# iF11M.net
KiCad netlist of a schematic drawn in Altium Designer
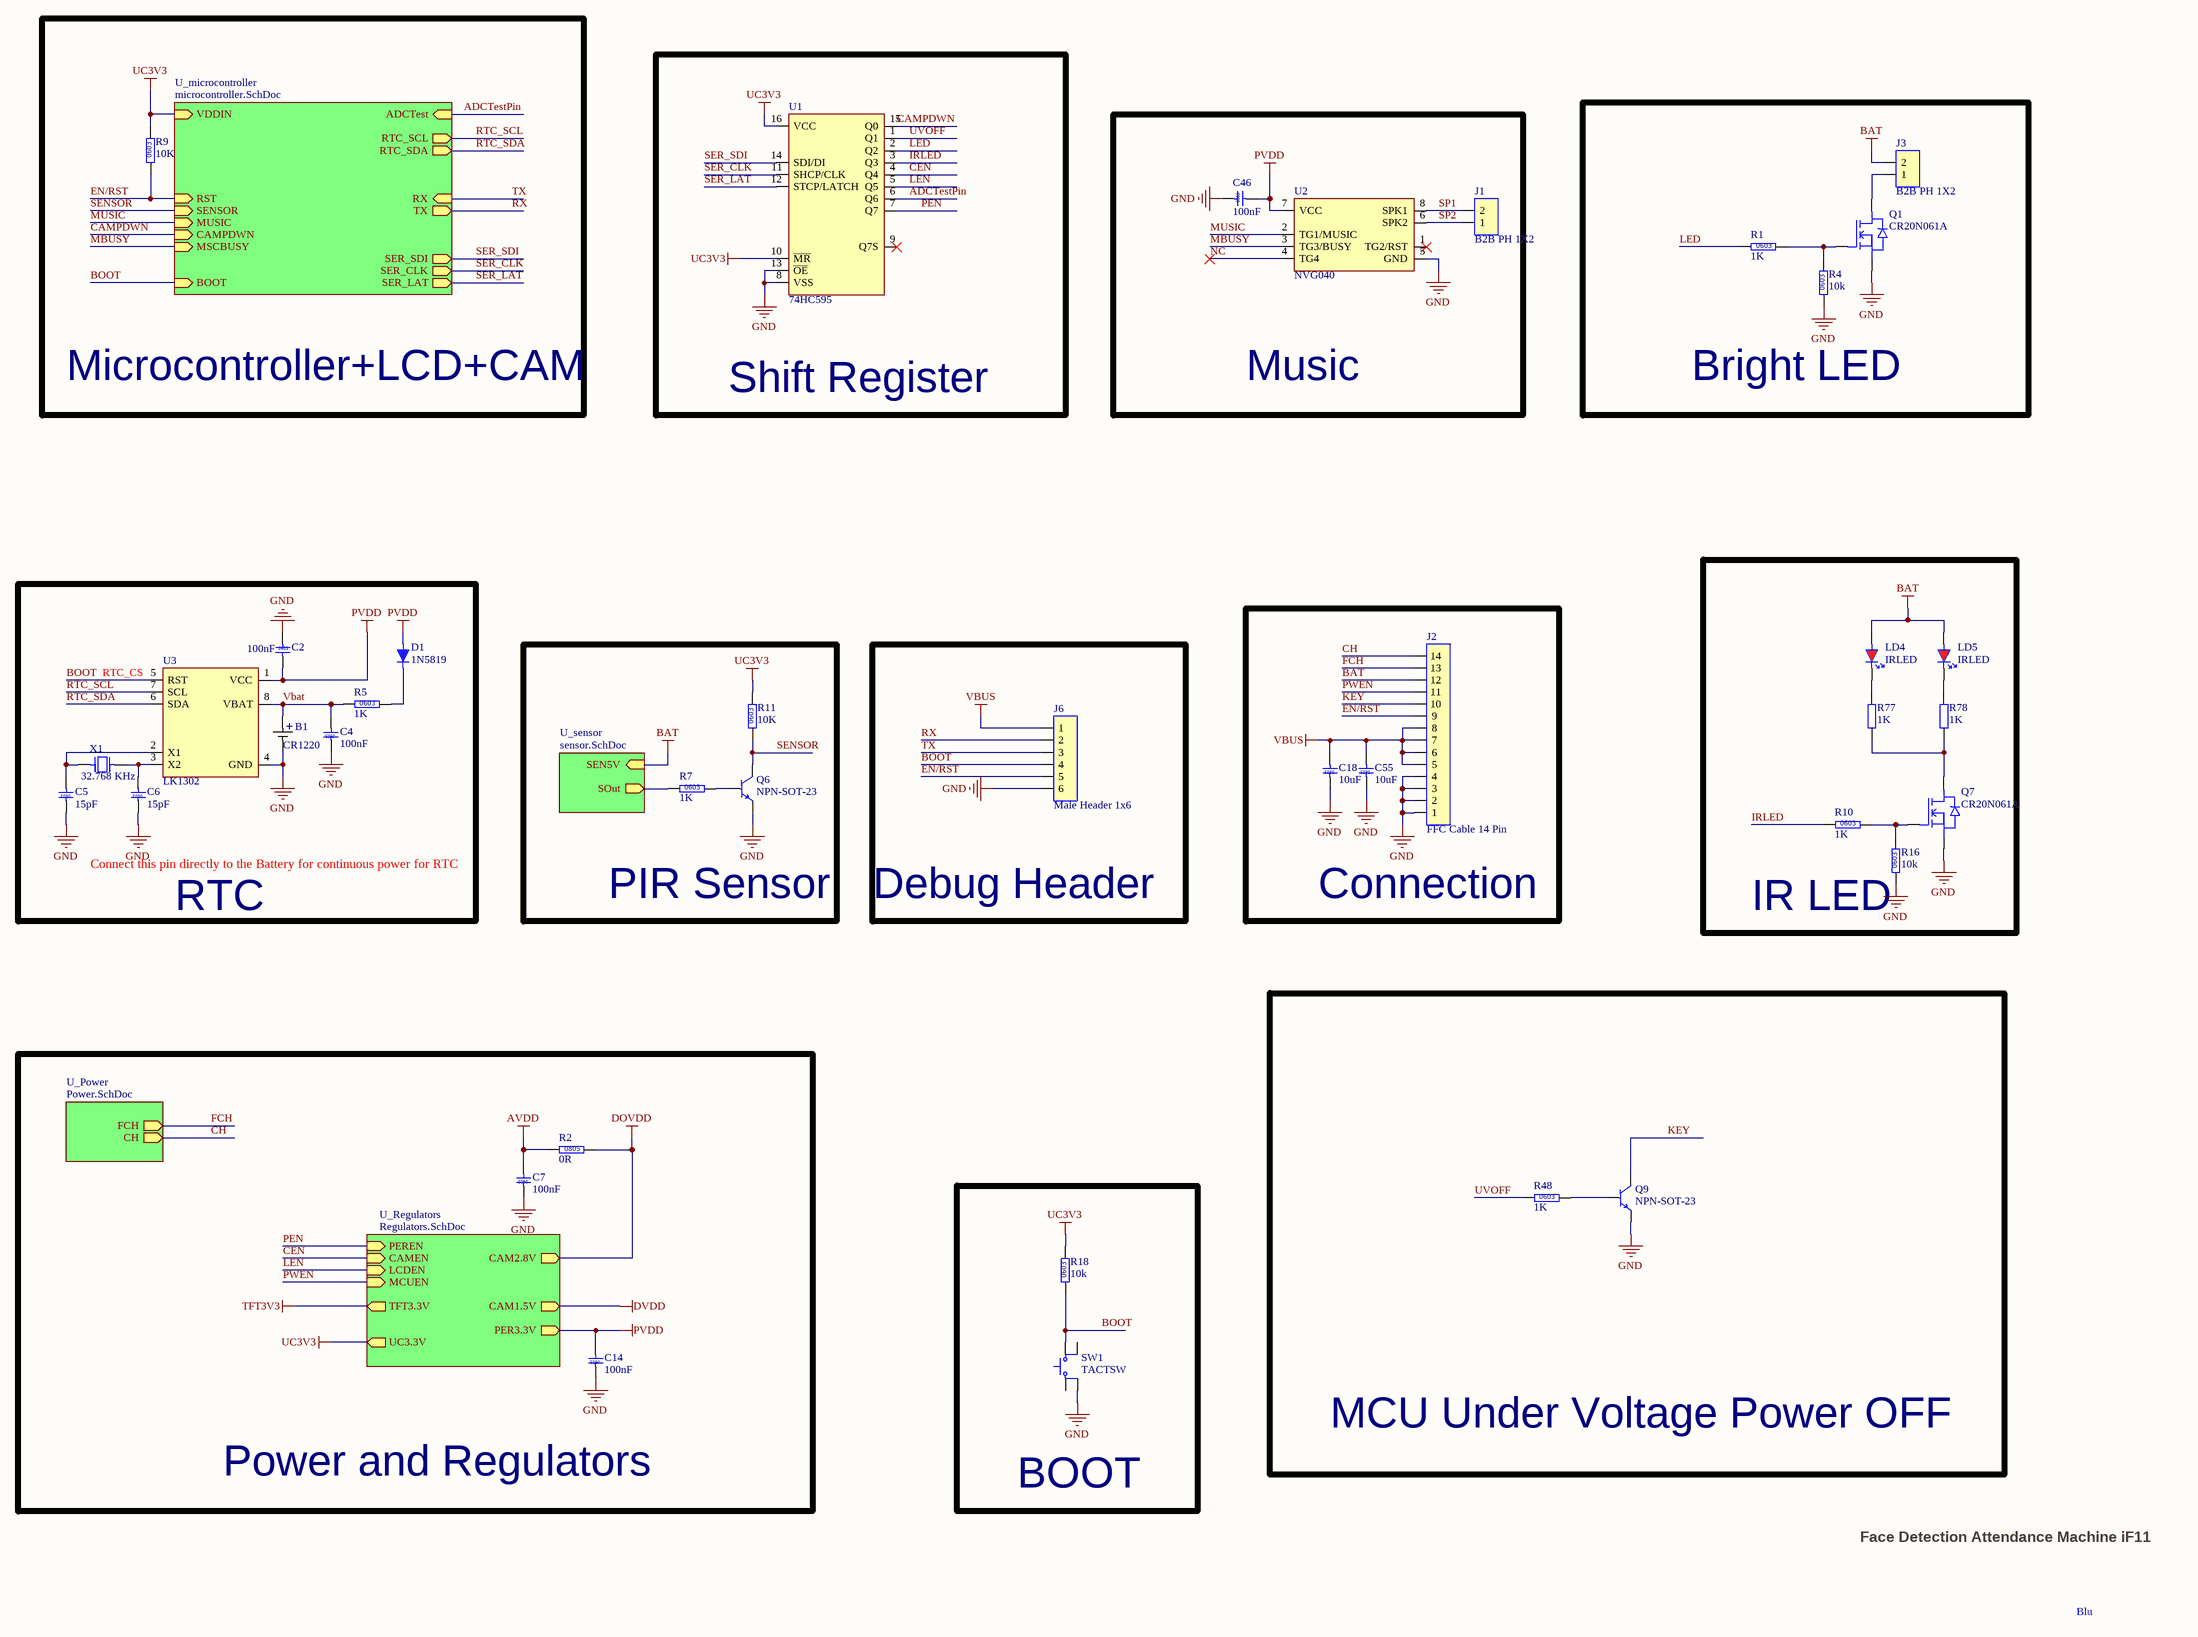
[diagram p0: iF11M.SchDoc]

(export (version "E")
  (design (tool "Eeschema 10.0.6"))
  (components
    (comp (ref "B1") (value "CR1220") (footprint "CR1220") (libsource (lib "Others") (part "CR1220")))
    (comp (ref "C2")
      (value "100nF")
      (footprint "C0603")
      (description "10% 50V")
      (fields (field (name "PART NO") "W-T-CA-X703N100K50VNT") (field (name "MANUFACTURER") "FENGHUA"))
      (libsource (lib "Rescap") (part "C 0603 100nF 50V"))
    )
    (comp (ref "C4")
      (value "100nF")
      (footprint "C0603")
      (description "10% 50V")
      (fields (field (name "PART NO") "W-T-CA-X703N100K50VNT") (field (name "MANUFACTURER") "FENGHUA"))
      (libsource (lib "Rescap") (part "C 0603 100nF 50V"))
    )
    (comp (ref "C5")
      (value "15pF")
      (footprint "C0603")
      (description "5% 25V")
      (fields (field (name "PART NO") "W-T-CA-CG03P010J25VNT"))
      (libsource (lib "Rescap") (part "C 0603 10pF 25V"))
    )
    (comp (ref "C6")
      (value "15pF")
      (footprint "C0603")
      (description "5% 25V")
      (fields (field (name "PART NO") "W-T-CA-CG03P010J25VNT"))
      (libsource (lib "Rescap") (part "C 0603 10pF 25V"))
    )
    (comp (ref "C7")
      (value "100nF")
      (footprint "C0603")
      (description "10% 50V")
      (fields (field (name "PART NO") "W-T-CA-X703N100K50VNT") (field (name "MANUFACTURER") "FENGHUA"))
      (libsource (lib "Rescap") (part "C 0603 100nF 50V"))
    )
    (comp (ref "C14")
      (value "100nF")
      (footprint "C0603")
      (description "10% 50V")
      (fields (field (name "PART NO") "W-T-CA-X703N100K50VNT") (field (name "MANUFACTURER") "FENGHUA"))
      (libsource (lib "Rescap") (part "C 0603 100nF 50V"))
    )
    (comp (ref "C18")
      (value "10uF")
      (footprint "C0805")
      (description "10% 25V")
      (fields (field (name "PART NO") "WP0005368"))
      (libsource (lib "Rescap") (part "C 0805 10uF 25V"))
    )
    (comp (ref "C46")
      (value "100nF")
      (footprint "C0603")
      (description "10% 50V")
      (fields (field (name "PART NO") "W-T-CA-X703N100K50VNT") (field (name "MANUFACTURER") "FENGHUA"))
      (libsource (lib "Rescap") (part "C 0603 100nF 50V"))
    )
    (comp (ref "C55")
      (value "10uF")
      (footprint "C0805")
      (description "10% 25V")
      (fields (field (name "PART NO") "WP0005368"))
      (libsource (lib "Rescap") (part "C 0805 10uF 25V"))
    )
    (comp (ref "D1") (value "1N5819") (footprint "SOD-323") (libsource (lib "Rectifier") (part "IN4148")))
    (comp (ref "J1")
      (value "B2B PH 1X2")
      (footprint "B2B-PH-2mm")
      (description "2 Pin B2B Connector")
      (libsource (lib "Connector") (part "B2B-PH-2MM"))
    )
    (comp (ref "J2")
      (value "FFC Cable 14 Pin")
      (footprint "FPC14P-1.2mm-THT")
      (libsource (lib "Connector") (part "FFC14P"))
    )
    (comp (ref "J3")
      (value "B2B PH 1X2")
      (footprint "B2B-PH-2mm")
      (description "2 Pin B2B Connector")
      (libsource (lib "Connector") (part "B2B-PH-2MM"))
    )
    (comp (ref "J6")
      (value "Male Header 1x6")
      (footprint "MHEADER-1x6")
      (description "6 Pin Male Header")
      (libsource (lib "Connector") (part "MHeader-1x6"))
    )
    (comp (ref "LD4")
      (value "IRLED")
      (footprint "LED 5mm RED Bent2")
      (libsource (lib "Optoelectronics") (part "IRLED"))
    )
    (comp (ref "LD5")
      (value "IRLED")
      (footprint "LED 5mm RED Bent2 Flipped")
      (libsource (lib "Optoelectronics") (part "IRLED"))
    )
    (comp (ref "Q1")
      (value "CR20N061A")
      (footprint "NMOS-SOT23")
      (description "MOSFET-N-Channel")
      (libsource (lib "Transistor") (part "MOSFET-N-Channel"))
    )
    (comp (ref "Q6")
      (value "NPN-SOT-23")
      (footprint "SOT23")
      (libsource (lib "Transistor") (part "NPN-SOT-23"))
    )
    (comp (ref "Q7")
      (value "CR20N061A")
      (footprint "NMOS-SOT23")
      (description "MOSFET-N-Channel")
      (libsource (lib "Transistor") (part "MOSFET-N-Channel"))
    )
    (comp (ref "Q9")
      (value "NPN-SOT-23")
      (footprint "SOT23")
      (libsource (lib "Transistor") (part "NPN-SOT-23"))
    )
    (comp (ref "R1")
      (value "1K")
      (footprint "R0603-LD")
      (description "5%")
      (fields (field (name "PART NO") "W-T-RE-RS03K103JT") (field (name "MANUFACTURER") "热敏D541V11增加1颗用量"))
      (libsource (lib "Rescap") (part "R 0603 10k"))
    )
    (comp (ref "R2")
      (value "0R")
      (footprint "R0805-LD")
      (description "1%")
      (fields (field (name "PART NO") "W-T-RE-RS05K0R0JT"))
      (libsource (lib "Rescap") (part "R 0805 0R"))
    )
    (comp (ref "R4")
      (value "10k")
      (footprint "R0603-LD")
      (description "5%")
      (fields (field (name "PART NO") "W-T-RE-RS03K103JT") (field (name "MANUFACTURER") "热敏D541V11增加1颗用量"))
      (libsource (lib "Rescap") (part "R 0603 10k"))
    )
    (comp (ref "R5")
      (value "1K")
      (footprint "R0603-LD")
      (description "5%")
      (fields (field (name "PART NO") "W-T-RE-RS03K103JT") (field (name "MANUFACTURER") "热敏D541V11增加1颗用量"))
      (libsource (lib "Rescap") (part "R 0603 10k"))
    )
    (comp (ref "R7")
      (value "1K")
      (footprint "R0603-LD")
      (description "5%")
      (fields (field (name "PART NO") "W-T-RE-RS03K103JT") (field (name "MANUFACTURER") "热敏D541V11增加1颗用量"))
      (libsource (lib "Rescap") (part "R 0603 10k"))
    )
    (comp (ref "R9")
      (value "10K")
      (footprint "R0603-LD")
      (description "5%")
      (fields (field (name "PART NO") "W-T-RE-RS03K103JT") (field (name "MANUFACTURER") "热敏D541V11增加1颗用量"))
      (libsource (lib "Rescap") (part "R 0603 10K"))
    )
    (comp (ref "R10")
      (value "1K")
      (footprint "R0603-LD")
      (description "5%")
      (fields (field (name "PART NO") "W-T-RE-RS03K103JT") (field (name "MANUFACTURER") "热敏D541V11增加1颗用量"))
      (libsource (lib "Rescap") (part "R 0603 10k"))
    )
    (comp (ref "R11")
      (value "10K")
      (footprint "R0603-LD")
      (description "5%")
      (fields (field (name "PART NO") "W-T-RE-RS03K103JT") (field (name "MANUFACTURER") "热敏D541V11增加1颗用量"))
      (libsource (lib "Rescap") (part "R 0603 10K"))
    )
    (comp (ref "R16")
      (value "10k")
      (footprint "R0603-LD")
      (description "5%")
      (fields (field (name "PART NO") "W-T-RE-RS03K103JT") (field (name "MANUFACTURER") "热敏D541V11增加1颗用量"))
      (libsource (lib "Rescap") (part "R 0603 10k"))
    )
    (comp (ref "R18")
      (value "10k")
      (footprint "R0603-LD")
      (description "5%")
      (fields (field (name "PART NO") "W-T-RE-RS03K103JT") (field (name "MANUFACTURER") "热敏D541V11增加1颗用量"))
      (libsource (lib "Rescap") (part "R 0603 10k"))
    )
    (comp (ref "R48")
      (value "1K")
      (footprint "R0603-LD")
      (description "5%")
      (fields (field (name "PART NO") "W-T-RE-RS03K102JT") (field (name "MANUFACTURER") "LAGEO"))
      (libsource (lib "Rescap") (part "R 0603 1K"))
    )
    (comp (ref "R77") (value "1K") (footprint "R0805") (libsource (lib "Resistor") (part "Resistor")))
    (comp (ref "R78") (value "1K") (footprint "R0805") (libsource (lib "Resistor") (part "Resistor")))
    (comp (ref "SW1")
      (value "TACTSW")
      (footprint "Button 6mm SMD")
      (description "2 pin tactile switch round")
      (libsource (lib "Switch") (part "Tactile-smd plastic"))
    )
    (comp (ref "U1")
      (value "74HC595")
      (footprint "SOIC16")
      (description "8bit Serial/Parallel Shift Register")
      (libsource (lib "mylib2") (part "74595"))
    )
    (comp (ref "U2") (value "NVG040") (footprint "SOP-8") (libsource (lib "mylib2") (part "NVG040")))
    (comp (ref "U3")
      (value "LK1302")
      (footprint "SOP-8")
      (description "Trickle-Charge Timekeeping Chip")
      (libsource (lib "mylib2") (part "LK1302"))
    )
    (comp (ref "X1")
      (value "32.768 KHz")
      (footprint "RTC Crystal")
      (description "RTC Crystal")
      (libsource (lib "Others") (part "Crystal_RTC"))
    )
  )
  (nets
    (net (code "1") (name "/ADCTestPin") (class "Default")
      (node (ref "U1") (pin "6") (pinfunction "Q6_6") (pintype "passive"))
    )
    (net (code "2") (name "/BOOT") (class "Default")
      (node (ref "J6") (pin "4") (pinfunction "4_4") (pintype "passive"))
      (node (ref "R18") (pin "1") (pinfunction "1_1") (pintype "passive"))
      (node (ref "SW1") (pin "4") (pinfunction "4_4") (pintype "passive"))
      (node (ref "U3") (pin "5") (pinfunction "RST_5") (pintype "passive"))
    )
    (net (code "3") (name "/CAMPDWN") (class "Default")
      (node (ref "U1") (pin "15") (pinfunction "Q0_15") (pintype "passive"))
    )
    (net (code "4") (name "/CEN") (class "Default")
      (node (ref "U1") (pin "4") (pinfunction "Q4_4") (pintype "passive"))
    )
    (net (code "5") (name "/CH") (class "Default")
      (node (ref "J2") (pin "14") (pinfunction "14_14") (pintype "passive"))
    )
    (net (code "6") (name "/EN{slash}RST") (class "Default")
      (node (ref "J2") (pin "9") (pinfunction "9_9") (pintype "passive"))
      (node (ref "J6") (pin "5") (pinfunction "5_5") (pintype "passive"))
      (node (ref "R9") (pin "1") (pinfunction "1_1") (pintype "passive"))
    )
    (net (code "7") (name "/FCH") (class "Default")
      (node (ref "J2") (pin "13") (pinfunction "13_13") (pintype "passive"))
    )
    (net (code "8") (name "/IRLED") (class "Default")
      (node (ref "R10") (pin "1") (pinfunction "1_1") (pintype "passive"))
      (node (ref "U1") (pin "3") (pinfunction "Q3_3") (pintype "passive"))
    )
    (net (code "9") (name "/KEY") (class "Default")
      (node (ref "J2") (pin "10") (pinfunction "10_10") (pintype "passive"))
      (node (ref "Q9") (pin "3") (pinfunction "C_3") (pintype "passive"))
    )
    (net (code "10") (name "/LED") (class "Default")
      (node (ref "R1") (pin "1") (pinfunction "1_1") (pintype "passive"))
      (node (ref "U1") (pin "2") (pinfunction "Q2_2") (pintype "passive"))
    )
    (net (code "11") (name "/LEN") (class "Default")
      (node (ref "U1") (pin "5") (pinfunction "Q5_5") (pintype "passive"))
    )
    (net (code "12") (name "/MBUSY") (class "Default")
      (node (ref "U2") (pin "3") (pinfunction "TG3/BUSY_3") (pintype "passive"))
    )
    (net (code "13") (name "/MUSIC") (class "Default")
      (node (ref "U2") (pin "2") (pinfunction "TG1/MUSIC_2") (pintype "passive"))
    )
    (net (code "14") (name "/NC") (class "Default")
      (node (ref "U2") (pin "4") (pinfunction "TG4_4") (pintype "passive+no_connect"))
    )
    (net (code "15") (name "/PEN") (class "Default")
      (node (ref "U1") (pin "7") (pinfunction "Q7_7") (pintype "passive"))
    )
    (net (code "16") (name "/PWEN") (class "Default")
      (node (ref "J2") (pin "11") (pinfunction "11_11") (pintype "passive"))
    )
    (net (code "17") (name "/RTC_SCL") (class "Default")
      (node (ref "U3") (pin "7") (pinfunction "SCL_7") (pintype "passive"))
    )
    (net (code "18") (name "/RTC_SDA") (class "Default")
      (node (ref "U3") (pin "6") (pinfunction "SDA_6") (pintype "passive"))
    )
    (net (code "19") (name "/RX") (class "Default")
      (node (ref "J6") (pin "2") (pinfunction "2_2") (pintype "passive"))
    )
    (net (code "20") (name "/SENSOR") (class "Default")
      (node (ref "Q6") (pin "3") (pinfunction "C_3") (pintype "passive"))
      (node (ref "R11") (pin "1") (pinfunction "1_1") (pintype "passive"))
    )
    (net (code "21") (name "/SER_CLK") (class "Default")
      (node (ref "U1") (pin "11") (pinfunction "SHCP/CLK_11") (pintype "passive"))
    )
    (net (code "22") (name "/SER_LAT") (class "Default")
      (node (ref "U1") (pin "12") (pinfunction "STCP/LATCH_12") (pintype "passive"))
    )
    (net (code "23") (name "/SER_SDI") (class "Default")
      (node (ref "U1") (pin "14") (pinfunction "SDI/DI_14") (pintype "passive"))
    )
    (net (code "24") (name "/SOut") (class "Default")
      (node (ref "R7") (pin "1") (pinfunction "1_1") (pintype "passive"))
    )
    (net (code "25") (name "/SP1") (class "Default")
      (node (ref "J1") (pin "2") (pinfunction "2_2") (pintype "passive"))
      (node (ref "U2") (pin "8") (pinfunction "SPK1_8") (pintype "passive"))
    )
    (net (code "26") (name "/SP2") (class "Default")
      (node (ref "J1") (pin "1") (pinfunction "1_1") (pintype "passive"))
      (node (ref "U2") (pin "6") (pinfunction "SPK2_6") (pintype "passive"))
    )
    (net (code "27") (name "/TX") (class "Default")
      (node (ref "J6") (pin "3") (pinfunction "3_3") (pintype "passive"))
    )
    (net (code "28") (name "/UVOFF") (class "Default")
      (node (ref "R48") (pin "1") (pinfunction "1_1") (pintype "passive"))
      (node (ref "U1") (pin "1") (pinfunction "Q1_1") (pintype "passive"))
    )
    (net (code "29") (name "/Vbat") (class "Default")
      (node (ref "B1") (pin "2") (pinfunction "2_2") (pintype "passive"))
      (node (ref "C4") (pin "2") (pinfunction "2_2") (pintype "passive"))
      (node (ref "R5") (pin "1") (pinfunction "1_1") (pintype "passive"))
      (node (ref "U3") (pin "8") (pinfunction "VBAT_8") (pintype "passive"))
    )
    (net (code "30") (name "AVDD") (class "Default")
      (node (ref "C7") (pin "2") (pinfunction "2_2") (pintype "passive"))
      (node (ref "R2") (pin "1") (pinfunction "1_1") (pintype "passive"))
    )
    (net (code "31") (name "BAT") (class "Default")
      (node (ref "J2") (pin "12") (pinfunction "12_12") (pintype "passive"))
      (node (ref "J3") (pin "2") (pinfunction "2_2") (pintype "passive"))
      (node (ref "LD4") (pin "1") (pinfunction "A_1") (pintype "passive"))
      (node (ref "LD5") (pin "1") (pinfunction "A_1") (pintype "passive"))
    )
    (net (code "32") (name "DOVDD") (class "Default")
      (node (ref "R2") (pin "2") (pinfunction "2_2") (pintype "passive"))
    )
    (net (code "34") (name "GND") (class "Default")
      (node (ref "B1") (pin "1") (pinfunction "1_1") (pintype "passive"))
      (node (ref "C14") (pin "1") (pinfunction "1_1") (pintype "passive"))
      (node (ref "C18") (pin "1") (pinfunction "1_1") (pintype "passive"))
      (node (ref "C2") (pin "1") (pinfunction "1_1") (pintype "passive"))
      (node (ref "C4") (pin "1") (pinfunction "1_1") (pintype "passive"))
      (node (ref "C46") (pin "1") (pinfunction "1_1") (pintype "passive"))
      (node (ref "C5") (pin "1") (pinfunction "1_1") (pintype "passive"))
      (node (ref "C55") (pin "1") (pinfunction "1_1") (pintype "passive"))
      (node (ref "C6") (pin "1") (pinfunction "1_1") (pintype "passive"))
      (node (ref "C7") (pin "1") (pinfunction "1_1") (pintype "passive"))
      (node (ref "J2") (pin "1") (pinfunction "1_1") (pintype "passive"))
      (node (ref "J2") (pin "2") (pinfunction "2_2") (pintype "passive"))
      (node (ref "J2") (pin "3") (pinfunction "3_3") (pintype "passive"))
      (node (ref "J2") (pin "4") (pinfunction "4_4") (pintype "passive"))
      (node (ref "J6") (pin "6") (pinfunction "6_6") (pintype "passive"))
      (node (ref "Q1") (pin "3") (pinfunction "S_3") (pintype "passive"))
      (node (ref "Q6") (pin "2") (pinfunction "E_2") (pintype "passive"))
      (node (ref "Q7") (pin "3") (pinfunction "S_3") (pintype "passive"))
      (node (ref "Q9") (pin "2") (pinfunction "E_2") (pintype "passive"))
      (node (ref "R16") (pin "1") (pinfunction "1_1") (pintype "passive"))
      (node (ref "R4") (pin "1") (pinfunction "1_1") (pintype "passive"))
      (node (ref "SW1") (pin "2") (pinfunction "2_2") (pintype "passive"))
      (node (ref "U1") (pin "13") (pinfunction "~{OE}_13") (pintype "passive"))
      (node (ref "U1") (pin "8") (pinfunction "VSS_8") (pintype "passive"))
      (node (ref "U2") (pin "5") (pinfunction "GND_5") (pintype "passive"))
      (node (ref "U3") (pin "4") (pinfunction "GND_4") (pintype "passive"))
    )
    (net (code "35") (name "Net-(D1-K)") (class "Default")
      (node (ref "D1") (pin "2") (pinfunction "K_2") (pintype "passive"))
      (node (ref "R5") (pin "2") (pinfunction "2_2") (pintype "passive"))
    )
    (net (code "36") (name "Net-(LD4-K)") (class "Default")
      (node (ref "LD4") (pin "2") (pinfunction "K_2") (pintype "passive"))
      (node (ref "R77") (pin "2") (pinfunction "2_2") (pintype "passive"))
    )
    (net (code "37") (name "Net-(LD5-K)") (class "Default")
      (node (ref "LD5") (pin "2") (pinfunction "K_2") (pintype "passive"))
      (node (ref "R78") (pin "2") (pinfunction "2_2") (pintype "passive"))
    )
    (net (code "38") (name "Net-(Q1-D)") (class "Default")
      (node (ref "J3") (pin "1") (pinfunction "1_1") (pintype "passive"))
      (node (ref "Q1") (pin "2") (pinfunction "D_2") (pintype "passive"))
    )
    (net (code "39") (name "Net-(Q1-G)") (class "Default")
      (node (ref "Q1") (pin "1") (pinfunction "G_1") (pintype "passive"))
      (node (ref "R1") (pin "2") (pinfunction "2_2") (pintype "passive"))
      (node (ref "R4") (pin "2") (pinfunction "2_2") (pintype "passive"))
    )
    (net (code "40") (name "Net-(Q6-B)") (class "Default")
      (node (ref "Q6") (pin "1") (pinfunction "B_1") (pintype "passive"))
      (node (ref "R7") (pin "2") (pinfunction "2_2") (pintype "passive"))
    )
    (net (code "41") (name "Net-(Q7-D)") (class "Default")
      (node (ref "Q7") (pin "2") (pinfunction "D_2") (pintype "passive"))
      (node (ref "R77") (pin "1") (pinfunction "1_1") (pintype "passive"))
      (node (ref "R78") (pin "1") (pinfunction "1_1") (pintype "passive"))
    )
    (net (code "42") (name "Net-(Q7-G)") (class "Default")
      (node (ref "Q7") (pin "1") (pinfunction "G_1") (pintype "passive"))
      (node (ref "R10") (pin "2") (pinfunction "2_2") (pintype "passive"))
      (node (ref "R16") (pin "2") (pinfunction "2_2") (pintype "passive"))
    )
    (net (code "43") (name "Net-(Q9-B)") (class "Default")
      (node (ref "Q9") (pin "1") (pinfunction "B_1") (pintype "passive"))
      (node (ref "R48") (pin "2") (pinfunction "2_2") (pintype "passive"))
    )
    (net (code "44") (name "Net-(U3-X1)") (class "Default")
      (node (ref "C5") (pin "2") (pinfunction "2_2") (pintype "passive"))
      (node (ref "U3") (pin "2") (pinfunction "X1_2") (pintype "passive"))
      (node (ref "X1") (pin "2") (pinfunction "2_2") (pintype "passive"))
    )
    (net (code "45") (name "Net-(U3-X2)") (class "Default")
      (node (ref "C6") (pin "2") (pinfunction "2_2") (pintype "passive"))
      (node (ref "U3") (pin "3") (pinfunction "X2_3") (pintype "passive"))
      (node (ref "X1") (pin "1") (pinfunction "1_1") (pintype "passive"))
    )
    (net (code "46") (name "PVDD") (class "Default")
      (node (ref "C14") (pin "2") (pinfunction "2_2") (pintype "passive"))
      (node (ref "C2") (pin "2") (pinfunction "2_2") (pintype "passive"))
      (node (ref "C46") (pin "2") (pinfunction "2_2") (pintype "passive"))
      (node (ref "D1") (pin "1") (pinfunction "A_1") (pintype "passive"))
      (node (ref "U2") (pin "7") (pinfunction "VCC_7") (pintype "passive"))
      (node (ref "U3") (pin "1") (pinfunction "VCC_1") (pintype "passive"))
    )
    (net (code "48") (name "UC3V3") (class "Default")
      (node (ref "R11") (pin "2") (pinfunction "2_2") (pintype "passive"))
      (node (ref "R18") (pin "2") (pinfunction "2_2") (pintype "passive"))
      (node (ref "R9") (pin "2") (pinfunction "2_2") (pintype "passive"))
      (node (ref "U1") (pin "10") (pinfunction "~{MR}_10") (pintype "passive"))
      (node (ref "U1") (pin "16") (pinfunction "VCC_16") (pintype "passive"))
    )
    (net (code "49") (name "VBUS") (class "Default")
      (node (ref "C18") (pin "2") (pinfunction "2_2") (pintype "passive"))
      (node (ref "C55") (pin "2") (pinfunction "2_2") (pintype "passive"))
      (node (ref "J2") (pin "5") (pinfunction "5_5") (pintype "passive"))
      (node (ref "J2") (pin "6") (pinfunction "6_6") (pintype "passive"))
      (node (ref "J2") (pin "7") (pinfunction "7_7") (pintype "passive"))
      (node (ref "J2") (pin "8") (pinfunction "8_8") (pintype "passive"))
      (node (ref "J6") (pin "1") (pinfunction "1_1") (pintype "passive"))
    )
    (net (code "50") (name "unconnected-(SW1-Pad1)") (class "Default")
      (node (ref "SW1") (pin "1") (pinfunction "1_1") (pintype "passive"))
    )
    (net (code "51") (name "unconnected-(SW1-Pad3)") (class "Default")
      (node (ref "SW1") (pin "3") (pinfunction "3_3") (pintype "passive"))
    )
    (net (code "52") (name "unconnected-(U1-Q7S-Pad9)") (class "Default")
      (node (ref "U1") (pin "9") (pinfunction "Q7S_9") (pintype "passive+no_connect"))
    )
    (net (code "53") (name "unconnected-(U2-TG2{slash}RST-Pad1)") (class "Default")
      (node (ref "U2") (pin "1") (pinfunction "TG2/RST_1") (pintype "passive+no_connect"))
    )
  )
)
